# Photon.net
KiCad netlist of a schematic drawn in Altium Designer
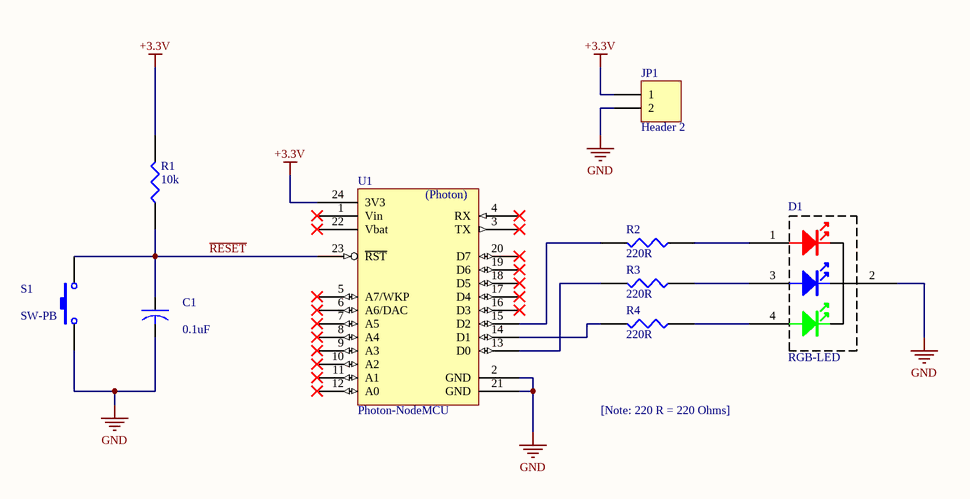
[diagram p0: Photon.SchDoc]

(export (version "E")
  (design (tool "Eeschema 10.0.6"))
  (components
    (comp (ref "C1")
      (value "0.1uF")
      (footprint "RAD0.2")
      (description "Non-polarized Electrolytic Capacitor")
      (libsource (lib "ECET231SCHLIB_Rev01") (part "CAPACITOR"))
    )
    (comp (ref "D1")
      (value "RGB-LED")
      (footprint "RGB-LED")
      (description "RGB Capable LED")
      (libsource (lib "ECET231SCHLIB_Rev01") (part "RGB-LED"))
    )
    (comp (ref "JP1")
      (value "Header 2")
      (footprint "HDR1X2")
      (description "Header, 2-Pin")
      (fields (field (name "PUBLISHER") "Altium Limited"))
      (libsource (lib "ECET231SCHLIB_Rev01") (part "Header 2"))
    )
    (comp (ref "R1")
      (value "10k")
      (footprint "axial0.5")
      (description "Resistor")
      (libsource (lib "ECET231SCHLIB_Rev01") (part "RES1"))
    )
    (comp (ref "R2")
      (value "220R")
      (footprint "axial0.5")
      (description "Resistor")
      (libsource (lib "ECET231SCHLIB_Rev01") (part "RES1"))
    )
    (comp (ref "R3")
      (value "220R")
      (footprint "axial0.5")
      (description "Resistor")
      (libsource (lib "ECET231SCHLIB_Rev01") (part "RES1"))
    )
    (comp (ref "R4")
      (value "220R")
      (footprint "axial0.5")
      (description "Resistor")
      (libsource (lib "ECET231SCHLIB_Rev01") (part "RES1"))
    )
    (comp (ref "S1")
      (value "SW-PB")
      (footprint "SPST-2")
      (description "Push-button Switch")
      (fields (field (name "PUBLISHER") "Altium Limited"))
      (libsource (lib "ECET231SCHLIB_Rev01") (part "SW-PB"))
    )
    (comp (ref "U1")
      (value "Photon-NodeMCU")
      (footprint "PHOTONNODE_TH")
      (libsource (lib "ECET231SCHLIB_Rev01") (part "Photon-NodeMCU"))
    )
  )
  (nets
    (net (code "1") (name "+3.3V") (class "Default")
      (node (ref "JP1") (pin "1") (pinfunction "1_1") (pintype "passive"))
      (node (ref "R1") (pin "2") (pinfunction "2_2") (pintype "passive"))
      (node (ref "U1") (pin "24") (pinfunction "3V3_24") (pintype "power_in"))
    )
    (net (code "2") (name "/~{RESET}") (class "Default")
      (node (ref "C1") (pin "1") (pinfunction "1_1") (pintype "passive"))
      (node (ref "R1") (pin "1") (pinfunction "1_1") (pintype "passive"))
      (node (ref "S1") (pin "2") (pinfunction "2_2") (pintype "passive"))
      (node (ref "U1") (pin "23") (pinfunction "~{RST}_23") (pintype "input"))
    )
    (net (code "3") (name "GND") (class "Default")
      (node (ref "C1") (pin "2") (pinfunction "2_2") (pintype "passive"))
      (node (ref "D1") (pin "2") (pintype "passive"))
      (node (ref "JP1") (pin "2") (pinfunction "2_2") (pintype "passive"))
      (node (ref "S1") (pin "1") (pinfunction "1_1") (pintype "passive"))
      (node (ref "U1") (pin "2") (pinfunction "GND_2") (pintype "power_in"))
      (node (ref "U1") (pin "21") (pinfunction "GND_21") (pintype "power_in"))
    )
    (net (code "4") (name "Net-(D1-Pad1)") (class "Default")
      (node (ref "D1") (pin "1") (pintype "passive"))
      (node (ref "R2") (pin "1") (pinfunction "1_1") (pintype "passive"))
    )
    (net (code "5") (name "Net-(D1-Pad3)") (class "Default")
      (node (ref "D1") (pin "3") (pintype "passive"))
      (node (ref "R3") (pin "1") (pinfunction "1_1") (pintype "passive"))
    )
    (net (code "6") (name "Net-(D1-Pad4)") (class "Default")
      (node (ref "D1") (pin "4") (pintype "passive"))
      (node (ref "R4") (pin "1") (pinfunction "1_1") (pintype "passive"))
    )
    (net (code "7") (name "Net-(U1-D0)") (class "Default")
      (node (ref "R3") (pin "2") (pinfunction "2_2") (pintype "passive"))
      (node (ref "U1") (pin "13") (pinfunction "D0_13") (pintype "bidirectional"))
    )
    (net (code "8") (name "Net-(U1-D1)") (class "Default")
      (node (ref "R4") (pin "2") (pinfunction "2_2") (pintype "passive"))
      (node (ref "U1") (pin "14") (pinfunction "D1_14") (pintype "bidirectional"))
    )
    (net (code "9") (name "Net-(U1-D2)") (class "Default")
      (node (ref "R2") (pin "2") (pinfunction "2_2") (pintype "passive"))
      (node (ref "U1") (pin "15") (pinfunction "D2_15") (pintype "bidirectional"))
    )
    (net (code "10") (name "unconnected-(U1-A0-Pad12)") (class "Default")
      (node (ref "U1") (pin "12") (pinfunction "A0_12") (pintype "bidirectional+no_connect"))
    )
    (net (code "11") (name "unconnected-(U1-A1-Pad11)") (class "Default")
      (node (ref "U1") (pin "11") (pinfunction "A1_11") (pintype "bidirectional+no_connect"))
    )
    (net (code "12") (name "unconnected-(U1-A2-Pad10)") (class "Default")
      (node (ref "U1") (pin "10") (pinfunction "A2_10") (pintype "bidirectional+no_connect"))
    )
    (net (code "13") (name "unconnected-(U1-A3-Pad9)") (class "Default")
      (node (ref "U1") (pin "9") (pinfunction "A3_9") (pintype "bidirectional+no_connect"))
    )
    (net (code "14") (name "unconnected-(U1-A4-Pad8)") (class "Default")
      (node (ref "U1") (pin "8") (pinfunction "A4_8") (pintype "bidirectional+no_connect"))
    )
    (net (code "15") (name "unconnected-(U1-A5-Pad7)") (class "Default")
      (node (ref "U1") (pin "7") (pinfunction "A5_7") (pintype "bidirectional+no_connect"))
    )
    (net (code "16") (name "unconnected-(U1-A6{slash}DAC-Pad6)") (class "Default")
      (node (ref "U1") (pin "6") (pinfunction "A6/DAC_6") (pintype "bidirectional+no_connect"))
    )
    (net (code "17") (name "unconnected-(U1-A7{slash}WKP-Pad5)") (class "Default")
      (node (ref "U1") (pin "5") (pinfunction "A7/WKP_5") (pintype "bidirectional+no_connect"))
    )
    (net (code "18") (name "unconnected-(U1-D3-Pad16)") (class "Default")
      (node (ref "U1") (pin "16") (pinfunction "D3_16") (pintype "bidirectional+no_connect"))
    )
    (net (code "19") (name "unconnected-(U1-D4-Pad17)") (class "Default")
      (node (ref "U1") (pin "17") (pinfunction "D4_17") (pintype "bidirectional+no_connect"))
    )
    (net (code "20") (name "unconnected-(U1-D5-Pad18)") (class "Default")
      (node (ref "U1") (pin "18") (pinfunction "D5_18") (pintype "bidirectional+no_connect"))
    )
    (net (code "21") (name "unconnected-(U1-D6-Pad19)") (class "Default")
      (node (ref "U1") (pin "19") (pinfunction "D6_19") (pintype "bidirectional+no_connect"))
    )
    (net (code "22") (name "unconnected-(U1-D7-Pad20)") (class "Default")
      (node (ref "U1") (pin "20") (pinfunction "D7_20") (pintype "bidirectional+no_connect"))
    )
    (net (code "23") (name "unconnected-(U1-RX-Pad4)") (class "Default")
      (node (ref "U1") (pin "4") (pinfunction "RX_4") (pintype "input+no_connect"))
    )
    (net (code "24") (name "unconnected-(U1-TX-Pad3)") (class "Default")
      (node (ref "U1") (pin "3") (pinfunction "TX_3") (pintype "output+no_connect"))
    )
    (net (code "25") (name "unconnected-(U1-Vbat-Pad22)") (class "Default")
      (node (ref "U1") (pin "22") (pinfunction "Vbat_22") (pintype "power_in+no_connect"))
    )
    (net (code "26") (name "unconnected-(U1-Vin-Pad1)") (class "Default")
      (node (ref "U1") (pin "1") (pinfunction "Vin_1") (pintype "power_in+no_connect"))
    )
  )
)
